# Cargador_RasPi3HAT_CamSlot_v2_1.net
KiCad netlist of a schematic drawn in EAGLE
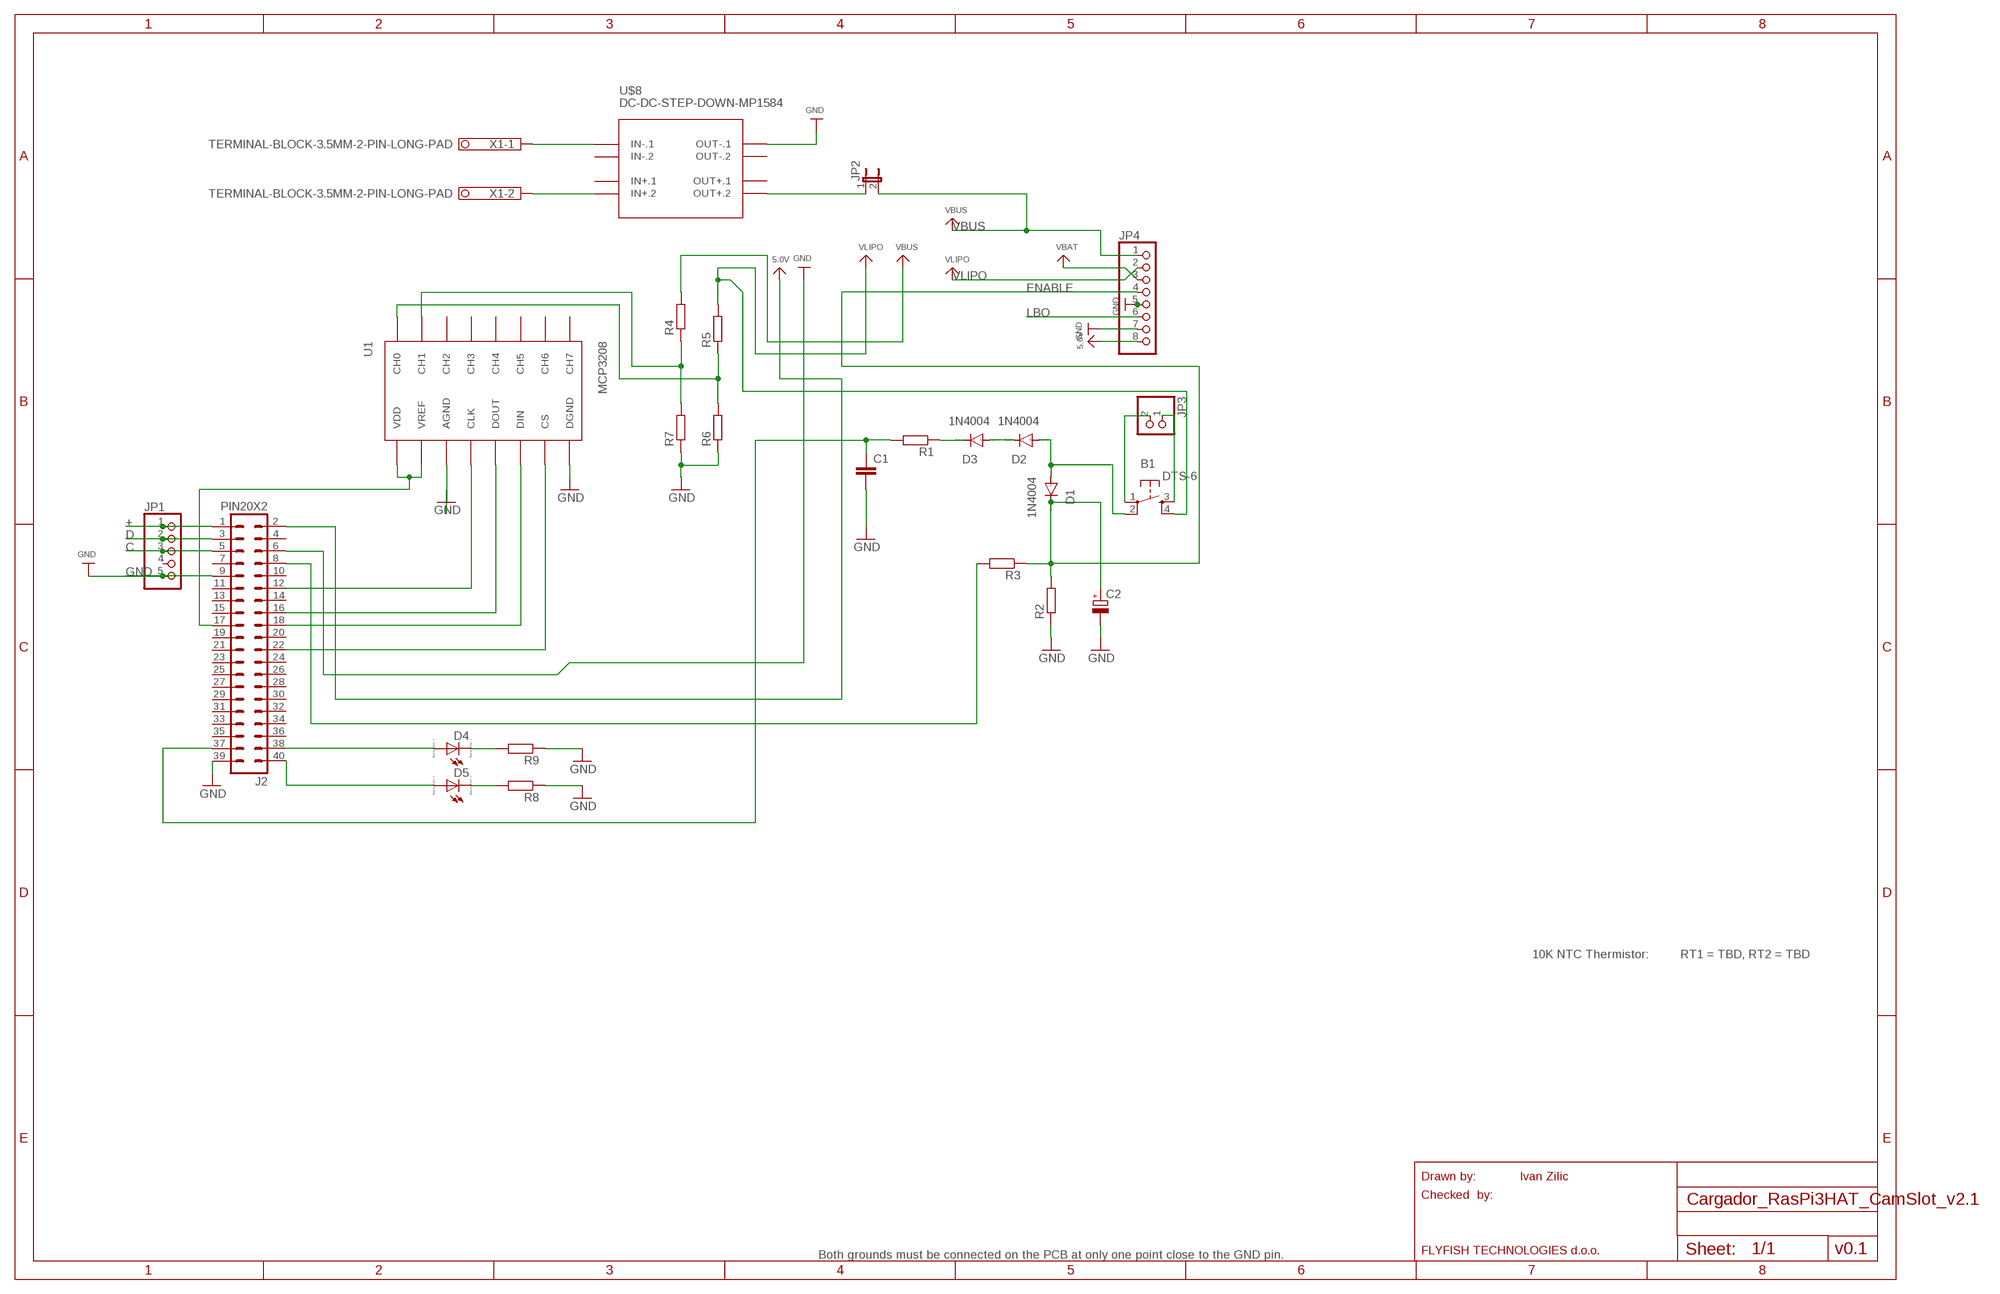
[diagram p0: schematic, sheet 1]

(export (version "E")
  (design (tool "Eeschema 10.0.6"))
  (components
    (comp (ref "B1")
      (value "DTS-6")
      (footprint "eagle-import:DTS-6")
      (libsource (lib "eagle-import") (part "DTS-6"))
    )
    (comp (ref "C1")
      (value "C2.5/2")
      (footprint "eagle-import:C2.5-2")
      (libsource (lib "eagle-import") (part "C2.5/2"))
    )
    (comp (ref "C2")
      (value "CPOL-EUE5-4")
      (footprint "eagle-import:E5-4")
      (libsource (lib "eagle-import") (part "CPOL-EUE5-4"))
    )
    (comp (ref "D1")
      (value "1N4004")
      (footprint "eagle-import:DO41-10")
      (libsource (lib "eagle-import") (part "1N4004"))
    )
    (comp (ref "D2")
      (value "1N4004")
      (footprint "eagle-import:DO41-10")
      (libsource (lib "eagle-import") (part "1N4004"))
    )
    (comp (ref "D3")
      (value "1N4004")
      (footprint "eagle-import:DO41-10")
      (libsource (lib "eagle-import") (part "1N4004"))
    )
    (comp (ref "D4")
      (value "LED_ELD260")
      (footprint "eagle-import:LED_LD260")
      (libsource (lib "eagle-import") (part "LED_ELD260"))
    )
    (comp (ref "D5")
      (value "LED_ELD260")
      (footprint "eagle-import:LED_LD260")
      (libsource (lib "eagle-import") (part "LED_ELD260"))
    )
    (comp (ref "J2")
      (value "PIN20X2")
      (footprint "eagle-import:PIN_20X2")
      (libsource (lib "eagle-import") (part "PIN20X2"))
    )
    (comp (ref "JP1")
      (value "PINHD-1X5")
      (footprint "eagle-import:1X05")
      (libsource (lib "eagle-import") (part "PINHD-1X5"))
    )
    (comp (ref "JP2")
      (value "JP1E")
      (footprint "eagle-import:JP1")
      (libsource (lib "eagle-import") (part "JP1E"))
    )
    (comp (ref "JP3")
      (value "PINHD-1X2")
      (footprint "eagle-import:1X02")
      (libsource (lib "eagle-import") (part "PINHD-1X2"))
    )
    (comp (ref "JP4")
      (value "HEADER-1X8")
      (footprint "eagle-import:1X08_OVAL")
      (libsource (lib "eagle-import") (part "HEADER-1X8"))
    )
    (comp (ref "R1")
      (value "R-EU_0207/10")
      (footprint "eagle-import:0207_10")
      (libsource (lib "eagle-import") (part "R-EU_0207/10"))
    )
    (comp (ref "R2")
      (value "R-EU_0207/10")
      (footprint "eagle-import:0207_10")
      (libsource (lib "eagle-import") (part "R-EU_0207/10"))
    )
    (comp (ref "R3")
      (value "R-EU_0207/10")
      (footprint "eagle-import:0207_10")
      (libsource (lib "eagle-import") (part "R-EU_0207/10"))
    )
    (comp (ref "R4")
      (value "R-EU_0207/10")
      (footprint "eagle-import:0207_10")
      (libsource (lib "eagle-import") (part "R-EU_0207/10"))
    )
    (comp (ref "R5")
      (value "R-EU_0207/10")
      (footprint "eagle-import:0207_10")
      (libsource (lib "eagle-import") (part "R-EU_0207/10"))
    )
    (comp (ref "R6")
      (value "R-EU_0207/10")
      (footprint "eagle-import:0207_10")
      (libsource (lib "eagle-import") (part "R-EU_0207/10"))
    )
    (comp (ref "R7")
      (value "R-EU_0207/10")
      (footprint "eagle-import:0207_10")
      (libsource (lib "eagle-import") (part "R-EU_0207/10"))
    )
    (comp (ref "R8")
      (value "R-EU_0207/10")
      (footprint "eagle-import:0207_10")
      (libsource (lib "eagle-import") (part "R-EU_0207/10"))
    )
    (comp (ref "R9")
      (value "R-EU_0207/10")
      (footprint "eagle-import:0207_10")
      (libsource (lib "eagle-import") (part "R-EU_0207/10"))
    )
    (comp (ref "U$8")
      (value "DC-DC-STEP-DOWN-MP1584")
      (footprint "eagle-import:DC-DC-STEP-DOWN-MP1584")
      (libsource (lib "eagle-import") (part "DC-DC-STEP-DOWN-MP1584"))
    )
    (comp (ref "U1")
      (value "MCP3208")
      (footprint "eagle-import:DIL16")
      (libsource (lib "eagle-import") (part "MCP3208"))
    )
    (comp (ref "X1")
      (value "TERMINAL-BLOCK-3.5MM-2-PIN-LONG-PAD")
      (footprint "eagle-import:TERMINAL-BLOCK-2-PIN-3.5MM-LONG-PAD")
      (libsource (lib "eagle-import") (part "TERMINAL-BLOCK-3.5MM-2-PIN-LONG-PAD"))
    )
  )
  (nets
    (net (code "1") (name "/+") (class "Default")
      (node (ref "J2") (pin "1") (pinfunction "1_1") (pintype "passive"))
      (node (ref "JP1") (pin "1") (pinfunction "1_1") (pintype "passive"))
    )
    (net (code "2") (name "/C") (class "Default")
      (node (ref "J2") (pin "5") (pinfunction "5_5") (pintype "passive"))
      (node (ref "JP1") (pin "3") (pinfunction "3_3") (pintype "passive"))
    )
    (net (code "3") (name "/D") (class "Default")
      (node (ref "J2") (pin "3") (pinfunction "3_3") (pintype "passive"))
      (node (ref "JP1") (pin "2") (pinfunction "2_2") (pintype "passive"))
    )
    (net (code "4") (name "/ENABLE") (class "Default")
      (node (ref "C2") (pin "+") (pinfunction "+_+") (pintype "passive"))
      (node (ref "D1") (pin "C") (pinfunction "C_C") (pintype "passive"))
      (node (ref "JP4") (pin "4") (pinfunction "4_4") (pintype "passive"))
      (node (ref "R2") (pin "2") (pinfunction "2_2") (pintype "passive"))
      (node (ref "R3") (pin "1") (pinfunction "1_1") (pintype "passive"))
    )
    (net (code "5") (name "/LBO") (class "Default")
      (node (ref "JP4") (pin "6") (pinfunction "6_6") (pintype "passive"))
    )
    (net (code "6") (name "5.0V") (class "Default")
      (node (ref "J2") (pin "2") (pinfunction "2_2") (pintype "passive"))
      (node (ref "JP4") (pin "8") (pinfunction "8_8") (pintype "passive"))
    )
    (net (code "7") (name "GND") (class "Default")
      (node (ref "C1") (pin "2") (pinfunction "2_2") (pintype "passive"))
      (node (ref "C2") (pin "-") (pinfunction "-_-") (pintype "passive"))
      (node (ref "J2") (pin "39") (pinfunction "39_39") (pintype "passive"))
      (node (ref "J2") (pin "6") (pinfunction "6_6") (pintype "passive"))
      (node (ref "J2") (pin "9") (pinfunction "9_9") (pintype "passive"))
      (node (ref "JP1") (pin "5") (pinfunction "5_5") (pintype "passive"))
      (node (ref "JP4") (pin "5") (pinfunction "5_5") (pintype "passive"))
      (node (ref "JP4") (pin "7") (pinfunction "7_7") (pintype "passive"))
      (node (ref "R2") (pin "1") (pinfunction "1_1") (pintype "passive"))
      (node (ref "R6") (pin "1") (pinfunction "1_1") (pintype "passive"))
      (node (ref "R7") (pin "1") (pinfunction "1_1") (pintype "passive"))
      (node (ref "R8") (pin "1") (pinfunction "1_1") (pintype "passive"))
      (node (ref "R9") (pin "1") (pinfunction "1_1") (pintype "passive"))
      (node (ref "U$8") (pin "OUT-.1") (pinfunction "OUT-.1_OUT-.1") (pintype "bidirectional"))
      (node (ref "U1") (pin "AGND") (pinfunction "AGND_AGND") (pintype "power_in"))
      (node (ref "U1") (pin "DGND") (pinfunction "DGND_DGND") (pintype "power_in"))
    )
    (net (code "8") (name "Net-(B1-Pad1)") (class "Default")
      (node (ref "B1") (pin "1") (pinfunction "1_1") (pintype "passive"))
      (node (ref "JP3") (pin "2") (pinfunction "2_2") (pintype "passive"))
    )
    (net (code "9") (name "Net-(B1-Pad2)") (class "Default")
      (node (ref "B1") (pin "2") (pinfunction "2_2") (pintype "passive"))
      (node (ref "D1") (pin "A") (pinfunction "A_A") (pintype "passive"))
      (node (ref "D2") (pin "A") (pinfunction "A_A") (pintype "passive"))
    )
    (net (code "10") (name "Net-(B1-Pad3)") (class "Default")
      (node (ref "B1") (pin "3") (pinfunction "3_3") (pintype "passive"))
      (node (ref "JP3") (pin "1") (pinfunction "1_1") (pintype "passive"))
    )
    (net (code "11") (name "Net-(C1-Pad1)") (class "Default")
      (node (ref "C1") (pin "1") (pinfunction "1_1") (pintype "passive"))
      (node (ref "J2") (pin "37") (pinfunction "37_37") (pintype "passive"))
      (node (ref "R1") (pin "2") (pinfunction "2_2") (pintype "passive"))
    )
    (net (code "12") (name "Net-(D2-PadC)") (class "Default")
      (node (ref "D2") (pin "C") (pinfunction "C_C") (pintype "passive"))
      (node (ref "D3") (pin "A") (pinfunction "A_A") (pintype "passive"))
    )
    (net (code "13") (name "Net-(D3-PadC)") (class "Default")
      (node (ref "D3") (pin "C") (pinfunction "C_C") (pintype "passive"))
      (node (ref "R1") (pin "1") (pinfunction "1_1") (pintype "passive"))
    )
    (net (code "14") (name "Net-(D4-C)") (class "Default")
      (node (ref "D4") (pin "K") (pinfunction "C_K") (pintype "passive"))
      (node (ref "R9") (pin "2") (pinfunction "2_2") (pintype "passive"))
    )
    (net (code "15") (name "Net-(D4-PadA)") (class "Default")
      (node (ref "D4") (pin "A") (pinfunction "A_A") (pintype "passive"))
      (node (ref "J2") (pin "38") (pinfunction "38_38") (pintype "passive"))
    )
    (net (code "16") (name "Net-(D5-C)") (class "Default")
      (node (ref "D5") (pin "K") (pinfunction "C_K") (pintype "passive"))
      (node (ref "R8") (pin "2") (pinfunction "2_2") (pintype "passive"))
    )
    (net (code "17") (name "Net-(D5-PadA)") (class "Default")
      (node (ref "D5") (pin "A") (pinfunction "A_A") (pintype "passive"))
      (node (ref "J2") (pin "40") (pinfunction "40_40") (pintype "passive"))
    )
    (net (code "18") (name "Net-(J2-Pad8)") (class "Default")
      (node (ref "J2") (pin "8") (pinfunction "8_8") (pintype "passive"))
      (node (ref "R3") (pin "2") (pinfunction "2_2") (pintype "passive"))
    )
    (net (code "19") (name "Net-(J2-Pad12)") (class "Default")
      (node (ref "J2") (pin "12") (pinfunction "12_12") (pintype "passive"))
      (node (ref "U1") (pin "CLK") (pinfunction "CLK_CLK") (pintype "input"))
    )
    (net (code "20") (name "Net-(J2-Pad16)") (class "Default")
      (node (ref "J2") (pin "16") (pinfunction "16_16") (pintype "passive"))
      (node (ref "U1") (pin "DOUT") (pinfunction "DOUT_DOUT") (pintype "output"))
    )
    (net (code "21") (name "Net-(J2-Pad17)") (class "Default")
      (node (ref "J2") (pin "17") (pinfunction "17_17") (pintype "passive"))
      (node (ref "U1") (pin "VDD") (pinfunction "VDD_VDD") (pintype "power_in"))
      (node (ref "U1") (pin "VREF") (pinfunction "VREF_VREF") (pintype "input"))
    )
    (net (code "22") (name "Net-(J2-Pad18)") (class "Default")
      (node (ref "J2") (pin "18") (pinfunction "18_18") (pintype "passive"))
      (node (ref "U1") (pin "DIN") (pinfunction "DIN_DIN") (pintype "input"))
    )
    (net (code "23") (name "Net-(J2-Pad22)") (class "Default")
      (node (ref "J2") (pin "22") (pinfunction "22_22") (pintype "passive"))
      (node (ref "U1") (pin "CS") (pinfunction "CS_CS") (pintype "input"))
    )
    (net (code "24") (name "Net-(JP2-Pad1)") (class "Default")
      (node (ref "JP2") (pin "1") (pinfunction "1_1") (pintype "passive"))
      (node (ref "U$8") (pin "OUT+.2") (pinfunction "OUT+.2_OUT+.2") (pintype "bidirectional"))
    )
    (net (code "25") (name "Net-(R4-Pad1)") (class "Default")
      (node (ref "R4") (pin "1") (pinfunction "1_1") (pintype "passive"))
      (node (ref "R7") (pin "2") (pinfunction "2_2") (pintype "passive"))
      (node (ref "U1") (pin "CH1") (pinfunction "CH1_CH1") (pintype "input"))
    )
    (net (code "26") (name "Net-(R5-Pad1)") (class "Default")
      (node (ref "R5") (pin "1") (pinfunction "1_1") (pintype "passive"))
      (node (ref "R6") (pin "2") (pinfunction "2_2") (pintype "passive"))
      (node (ref "U1") (pin "CH0") (pinfunction "CH0_CH0") (pintype "input"))
    )
    (net (code "27") (name "Net-(X1A-K)") (class "Default")
      (node (ref "U$8") (pin "IN-.1") (pinfunction "IN-.1_IN-.1") (pintype "bidirectional"))
      (node (ref "X1") (pin "1") (pinfunction "K_1") (pintype "passive"))
    )
    (net (code "28") (name "Net-(X1B-K)") (class "Default")
      (node (ref "U$8") (pin "IN+.2") (pinfunction "IN+.2_IN+.2") (pintype "bidirectional"))
      (node (ref "X1") (pin "2") (pinfunction "K_2") (pintype "passive"))
    )
    (net (code "29") (name "VBAT") (class "Default")
      (node (ref "JP4") (pin "3") (pinfunction "3_3") (pintype "passive"))
    )
    (net (code "30") (name "VBUS") (class "Default")
      (node (ref "JP2") (pin "2") (pinfunction "2_2") (pintype "passive"))
      (node (ref "JP4") (pin "1") (pinfunction "1_1") (pintype "passive"))
      (node (ref "R4") (pin "2") (pinfunction "2_2") (pintype "passive"))
    )
    (net (code "31") (name "VLIPO") (class "Default")
      (node (ref "B1") (pin "4") (pinfunction "4_4") (pintype "passive"))
      (node (ref "JP4") (pin "2") (pinfunction "2_2") (pintype "passive"))
      (node (ref "R5") (pin "2") (pinfunction "2_2") (pintype "passive"))
    )
    (net (code "32") (name "unconnected-(J2-Pad4)") (class "Default")
      (node (ref "J2") (pin "4") (pinfunction "4_4") (pintype "passive"))
    )
    (net (code "33") (name "unconnected-(J2-Pad7)") (class "Default")
      (node (ref "J2") (pin "7") (pinfunction "7_7") (pintype "passive"))
    )
    (net (code "34") (name "unconnected-(J2-Pad10)") (class "Default")
      (node (ref "J2") (pin "10") (pinfunction "10_10") (pintype "passive"))
    )
    (net (code "35") (name "unconnected-(J2-Pad11)") (class "Default")
      (node (ref "J2") (pin "11") (pinfunction "11_11") (pintype "passive"))
    )
    (net (code "36") (name "unconnected-(J2-Pad13)") (class "Default")
      (node (ref "J2") (pin "13") (pinfunction "13_13") (pintype "passive"))
    )
    (net (code "37") (name "unconnected-(J2-Pad14)") (class "Default")
      (node (ref "J2") (pin "14") (pinfunction "14_14") (pintype "passive"))
    )
    (net (code "38") (name "unconnected-(J2-Pad15)") (class "Default")
      (node (ref "J2") (pin "15") (pinfunction "15_15") (pintype "passive"))
    )
    (net (code "39") (name "unconnected-(J2-Pad19)") (class "Default")
      (node (ref "J2") (pin "19") (pinfunction "19_19") (pintype "passive"))
    )
    (net (code "40") (name "unconnected-(J2-Pad20)") (class "Default")
      (node (ref "J2") (pin "20") (pinfunction "20_20") (pintype "passive"))
    )
    (net (code "41") (name "unconnected-(J2-Pad21)") (class "Default")
      (node (ref "J2") (pin "21") (pinfunction "21_21") (pintype "passive"))
    )
    (net (code "42") (name "unconnected-(J2-Pad23)") (class "Default")
      (node (ref "J2") (pin "23") (pinfunction "23_23") (pintype "passive"))
    )
    (net (code "43") (name "unconnected-(J2-Pad24)") (class "Default")
      (node (ref "J2") (pin "24") (pinfunction "24_24") (pintype "passive"))
    )
    (net (code "44") (name "unconnected-(J2-Pad25)") (class "Default")
      (node (ref "J2") (pin "25") (pinfunction "25_25") (pintype "passive"))
    )
    (net (code "45") (name "unconnected-(J2-Pad26)") (class "Default")
      (node (ref "J2") (pin "26") (pinfunction "26_26") (pintype "passive"))
    )
    (net (code "46") (name "unconnected-(J2-Pad27)") (class "Default")
      (node (ref "J2") (pin "27") (pinfunction "27_27") (pintype "passive"))
    )
    (net (code "47") (name "unconnected-(J2-Pad28)") (class "Default")
      (node (ref "J2") (pin "28") (pinfunction "28_28") (pintype "passive"))
    )
    (net (code "48") (name "unconnected-(J2-Pad29)") (class "Default")
      (node (ref "J2") (pin "29") (pinfunction "29_29") (pintype "passive"))
    )
    (net (code "49") (name "unconnected-(J2-Pad30)") (class "Default")
      (node (ref "J2") (pin "30") (pinfunction "30_30") (pintype "passive"))
    )
    (net (code "50") (name "unconnected-(J2-Pad31)") (class "Default")
      (node (ref "J2") (pin "31") (pinfunction "31_31") (pintype "passive"))
    )
    (net (code "51") (name "unconnected-(J2-Pad32)") (class "Default")
      (node (ref "J2") (pin "32") (pinfunction "32_32") (pintype "passive"))
    )
    (net (code "52") (name "unconnected-(J2-Pad33)") (class "Default")
      (node (ref "J2") (pin "33") (pinfunction "33_33") (pintype "passive"))
    )
    (net (code "53") (name "unconnected-(J2-Pad34)") (class "Default")
      (node (ref "J2") (pin "34") (pinfunction "34_34") (pintype "passive"))
    )
    (net (code "54") (name "unconnected-(J2-Pad35)") (class "Default")
      (node (ref "J2") (pin "35") (pinfunction "35_35") (pintype "passive"))
    )
    (net (code "55") (name "unconnected-(J2-Pad36)") (class "Default")
      (node (ref "J2") (pin "36") (pinfunction "36_36") (pintype "passive"))
    )
    (net (code "56") (name "unconnected-(JP1-Pad4)") (class "Default")
      (node (ref "JP1") (pin "4") (pinfunction "4_4") (pintype "passive"))
    )
    (net (code "57") (name "unconnected-(U$8-PadIN+.1)") (class "Default")
      (node (ref "U$8") (pin "IN+.1") (pinfunction "IN+.1_IN+.1") (pintype "bidirectional"))
    )
    (net (code "58") (name "unconnected-(U$8-PadIN-.2)") (class "Default")
      (node (ref "U$8") (pin "IN-.2") (pinfunction "IN-.2_IN-.2") (pintype "bidirectional"))
    )
    (net (code "59") (name "unconnected-(U$8-PadOUT+.1)") (class "Default")
      (node (ref "U$8") (pin "OUT+.1") (pinfunction "OUT+.1_OUT+.1") (pintype "bidirectional"))
    )
    (net (code "60") (name "unconnected-(U$8-PadOUT-.2)") (class "Default")
      (node (ref "U$8") (pin "OUT-.2") (pinfunction "OUT-.2_OUT-.2") (pintype "bidirectional"))
    )
    (net (code "61") (name "unconnected-(U1-PadCH2)") (class "Default")
      (node (ref "U1") (pin "CH2") (pinfunction "CH2_CH2") (pintype "input"))
    )
    (net (code "62") (name "unconnected-(U1-PadCH3)") (class "Default")
      (node (ref "U1") (pin "CH3") (pinfunction "CH3_CH3") (pintype "input"))
    )
    (net (code "63") (name "unconnected-(U1-PadCH4)") (class "Default")
      (node (ref "U1") (pin "CH4") (pinfunction "CH4_CH4") (pintype "input"))
    )
    (net (code "64") (name "unconnected-(U1-PadCH5)") (class "Default")
      (node (ref "U1") (pin "CH5") (pinfunction "CH5_CH5") (pintype "input"))
    )
    (net (code "65") (name "unconnected-(U1-PadCH6)") (class "Default")
      (node (ref "U1") (pin "CH6") (pinfunction "CH6_CH6") (pintype "input"))
    )
    (net (code "66") (name "unconnected-(U1-PadCH7)") (class "Default")
      (node (ref "U1") (pin "CH7") (pinfunction "CH7_CH7") (pintype "input"))
    )
  )
)
